# iridia-tam-left-board.net
KiCad netlist of a schematic drawn in EAGLE
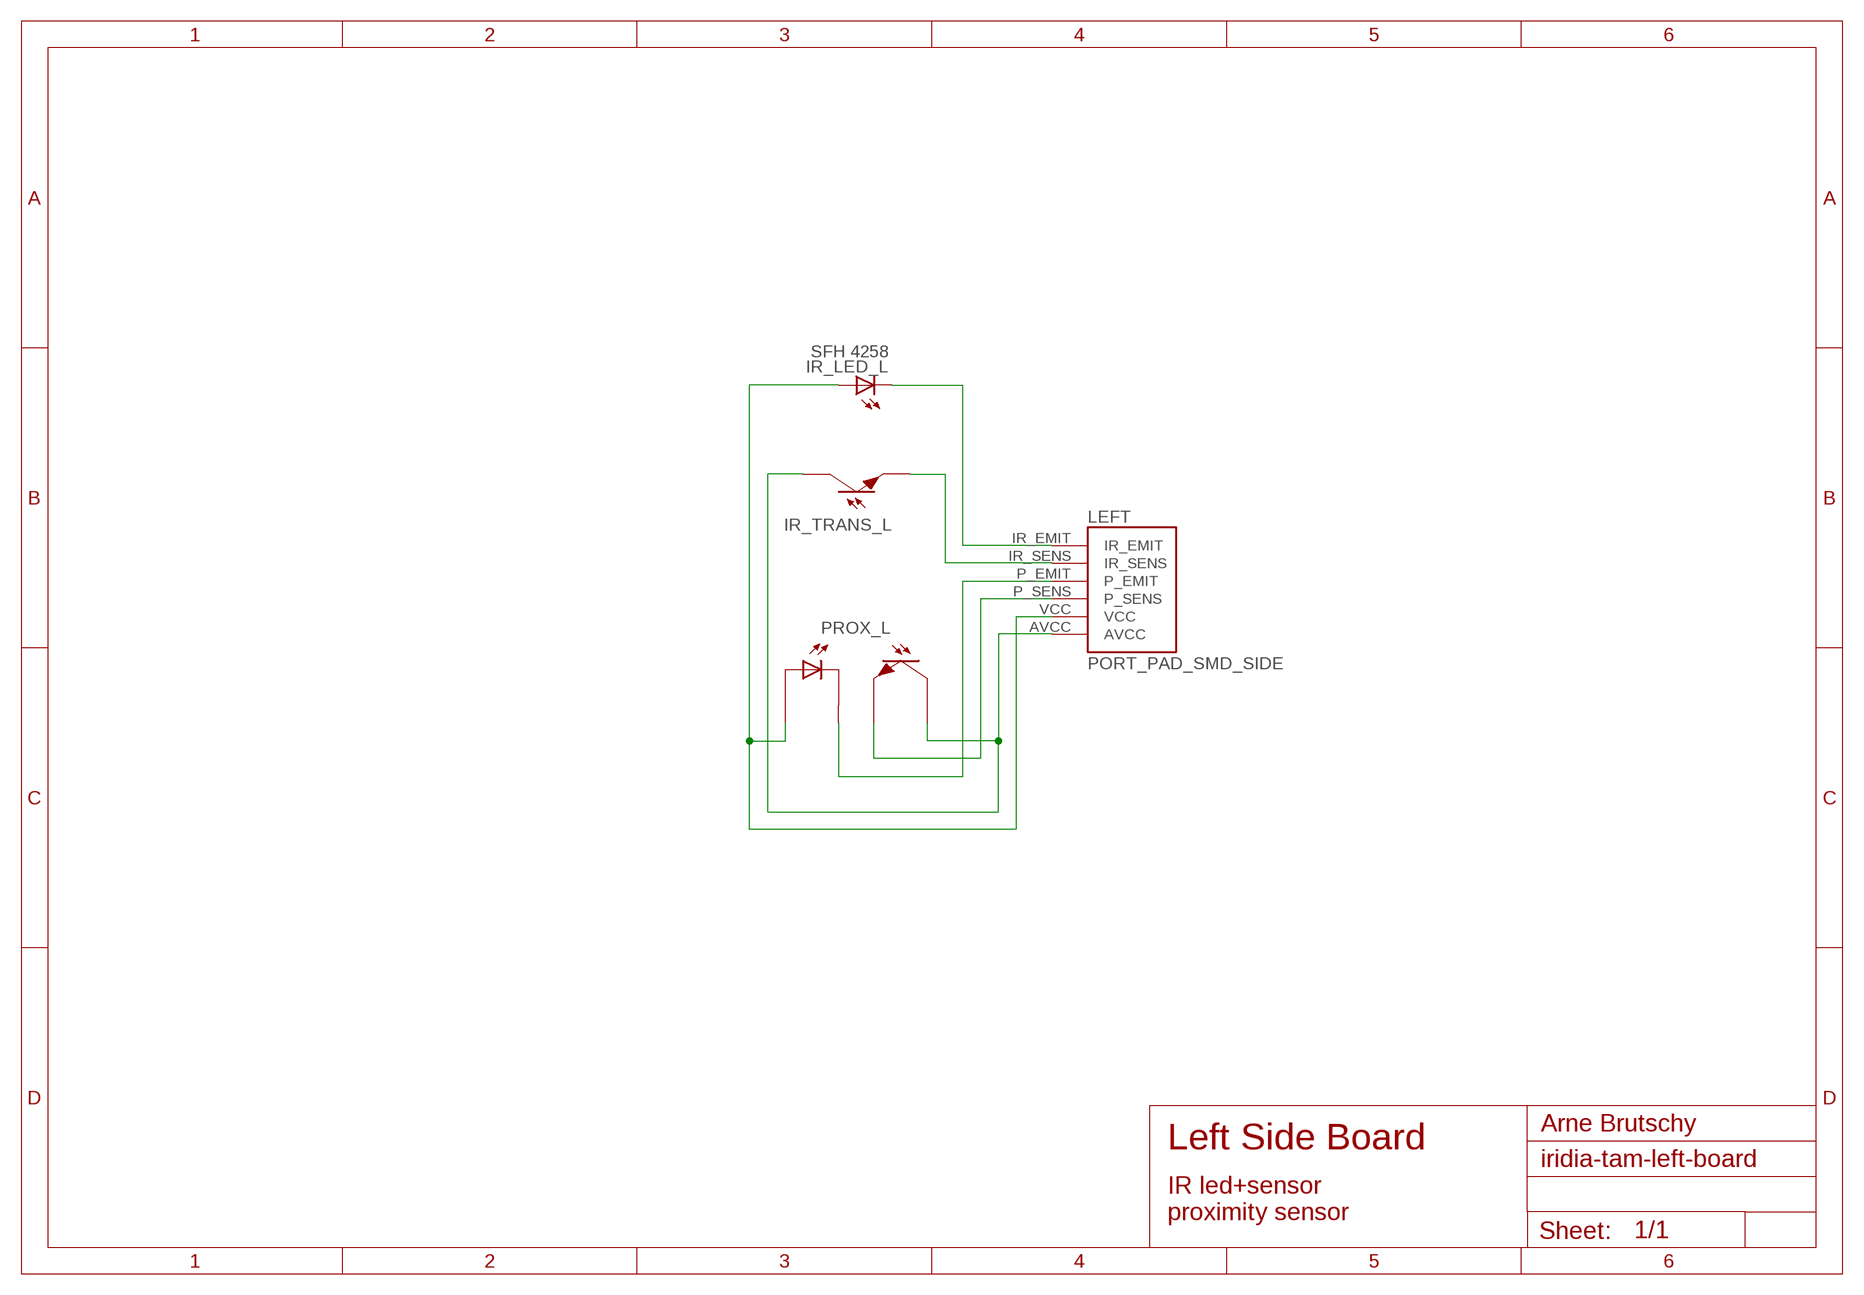
[diagram p0: schematic, sheet 1]

(export (version "E")
  (design (tool "Eeschema 10.0.6"))
  (components
    (comp (ref "IR_LED_L")
      (value "SFH 4258")
      (footprint "eagle-import:P-LCC-4-1C-3A")
      (libsource (lib "eagle-import") (part "LEDP-LCC-4"))
    )
    (comp (ref "IR_TRANS_L")
      (value "SFH 320 FA")
      (footprint "eagle-import:P-LCC-2-TRANS")
      (libsource (lib "eagle-import") (part "IR_TRANSP-LCC-2"))
    )
    (comp (ref "LEFT")
      (value "PORT_PAD_SMD_SIDE")
      (footprint "eagle-import:PORT_PAD_SMD_SIDE")
      (libsource (lib "eagle-import") (part "PORT_PAD_SMD_SIDE"))
    )
    (comp (ref "PROX_L")
      (value "TCRT1000")
      (footprint "eagle-import:TCRT1000_TH")
      (libsource (lib "eagle-import") (part "TCRT1000_TH"))
    )
  )
  (nets
    (net (code "1") (name "Net-(IR_LED_L-A-PadA@2)") (class "Default")
      (node (ref "IR_LED_L") (pin "A@2") (pinfunction "A_A@2") (pintype "passive"))
      (node (ref "IR_LED_L") (pin "A@3") (pinfunction "A_A@3") (pintype "passive"))
      (node (ref "IR_LED_L") (pin "A@4") (pinfunction "A_A@4") (pintype "passive"))
      (node (ref "LEFT") (pin "VCC") (pinfunction "VCC_VCC") (pintype "bidirectional"))
      (node (ref "PROX_L") (pin "A") (pinfunction "A_A") (pintype "passive"))
    )
    (net (code "2") (name "Net-(IR_LED_L-C)") (class "Default")
      (node (ref "IR_LED_L") (pin "C@1") (pinfunction "C_C@1") (pintype "passive"))
      (node (ref "LEFT") (pin "IR_EMIT") (pinfunction "IR_EMIT_IR_EMIT") (pintype "bidirectional"))
    )
    (net (code "3") (name "Net-(IR_TRANS_L-PadCOL)") (class "Default")
      (node (ref "IR_TRANS_L") (pin "COL") (pinfunction "COL_COL") (pintype "passive"))
      (node (ref "LEFT") (pin "AVCC") (pinfunction "AVCC_AVCC") (pintype "bidirectional"))
      (node (ref "PROX_L") (pin "COL") (pinfunction "COL_COL") (pintype "passive"))
    )
    (net (code "4") (name "Net-(IR_TRANS_L-PadE)") (class "Default")
      (node (ref "IR_TRANS_L") (pin "E") (pinfunction "E_E") (pintype "passive"))
      (node (ref "LEFT") (pin "IR_SENS") (pinfunction "IR_SENS_IR_SENS") (pintype "bidirectional"))
    )
    (net (code "5") (name "Net-(LEFT-PadP_EMIT)") (class "Default")
      (node (ref "LEFT") (pin "P_EMIT") (pinfunction "P_EMIT_P_EMIT") (pintype "bidirectional"))
      (node (ref "PROX_L") (pin "CAT") (pinfunction "CAT_CAT") (pintype "passive"))
    )
    (net (code "6") (name "Net-(LEFT-PadP_SENS)") (class "Default")
      (node (ref "LEFT") (pin "P_SENS") (pinfunction "P_SENS_P_SENS") (pintype "bidirectional"))
      (node (ref "PROX_L") (pin "E") (pinfunction "E_E") (pintype "passive"))
    )
  )
)
